# Tester_Schematic.net
KiCad netlist of a schematic drawn in EAGLE
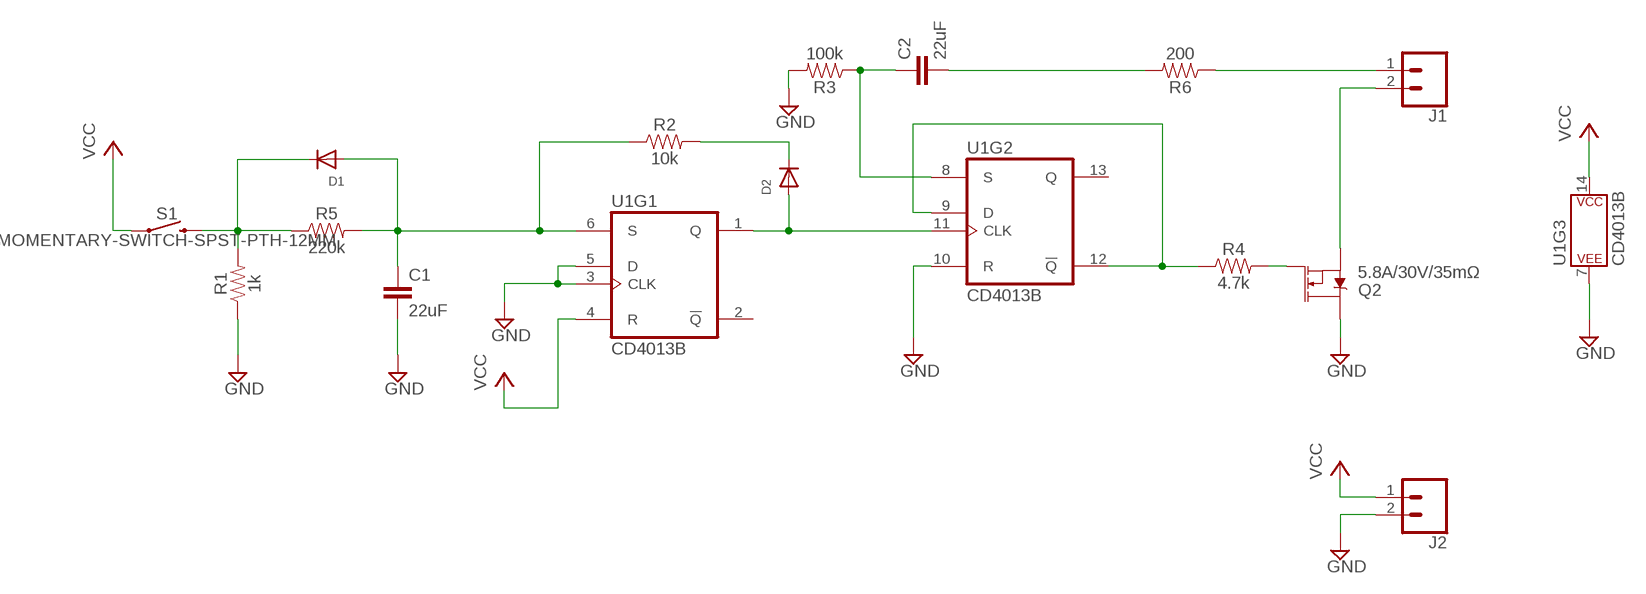
[diagram p0: schematic, sheet 1]

(export (version "E")
  (design (tool "Eeschema 10.0.6"))
  (components
    (comp (ref "C1")
      (value "22uF")
      (footprint "eagle-import:0805")
      (libsource (lib "eagle-import") (part "22UF-0805-6.3V-20%"))
    )
    (comp (ref "C2")
      (value "22uF")
      (footprint "eagle-import:0805")
      (libsource (lib "eagle-import") (part "22UF-0805-6.3V-20%"))
    )
    (comp (ref "D1")
      (value "DIODESOD-123")
      (footprint "eagle-import:SOD-123")
      (libsource (lib "eagle-import") (part "DIODESOD-123"))
    )
    (comp (ref "D2")
      (value "DIODESOD-123")
      (footprint "eagle-import:SOD-123")
      (libsource (lib "eagle-import") (part "DIODESOD-123"))
    )
    (comp (ref "J1")
      (value "CONN_02")
      (footprint "eagle-import:1X02")
      (libsource (lib "eagle-import") (part "CONN_02"))
    )
    (comp (ref "J2")
      (value "CONN_02")
      (footprint "eagle-import:1X02")
      (libsource (lib "eagle-import") (part "CONN_02"))
    )
    (comp (ref "Q2")
      (value "5.8A/30V/35mΩ")
      (footprint "eagle-import:SOT23-3")
      (libsource (lib "eagle-import") (part "MOSFET-NCH-AO3404A"))
    )
    (comp (ref "R1")
      (value "1k")
      (footprint "eagle-import:0603")
      (libsource (lib "eagle-import") (part "1KOHM-0603-1/10W-1%"))
    )
    (comp (ref "R2")
      (value "10k")
      (footprint "eagle-import:0603")
      (libsource (lib "eagle-import") (part "10KOHM-0603-1/10W-1%"))
    )
    (comp (ref "R3")
      (value "100k")
      (footprint "eagle-import:0603")
      (libsource (lib "eagle-import") (part "100KOHM-0603-1/10W-1%"))
    )
    (comp (ref "R4")
      (value "4.7k")
      (footprint "eagle-import:0603")
      (libsource (lib "eagle-import") (part "4.7KOHM-0603-1/10W-1%"))
    )
    (comp (ref "R5")
      (value "220k")
      (footprint "eagle-import:0603")
      (libsource (lib "eagle-import") (part "220KOHM-0603-1/10W-1%"))
    )
    (comp (ref "R6")
      (value "200")
      (footprint "eagle-import:0603")
      (libsource (lib "eagle-import") (part "200OHM-0603-1/10W-1%"))
    )
    (comp (ref "S1")
      (value "MOMENTARY-SWITCH-SPST-PTH-12MM")
      (footprint "eagle-import:TACTILE_SWITCH_PTH_12MM")
      (libsource (lib "eagle-import") (part "MOMENTARY-SWITCH-SPST-PTH-12MM"))
    )
    (comp (ref "U1")
      (value "CD4013B")
      (footprint "eagle-import:DIP14-KIT")
      (libsource (lib "eagle-import") (part "CD4013"))
    )
  )
  (nets
    (net (code "1") (name "GND") (class "Default")
      (node (ref "C1") (pin "2") (pinfunction "2_2") (pintype "passive"))
      (node (ref "J2") (pin "2") (pinfunction "2_2") (pintype "passive"))
      (node (ref "Q2") (pin "3") (pinfunction "D_3") (pintype "bidirectional"))
      (node (ref "R1") (pin "1") (pinfunction "1_1") (pintype "passive"))
      (node (ref "R3") (pin "2") (pinfunction "2_2") (pintype "passive"))
      (node (ref "U1") (pin "10") (pinfunction "R_10") (pintype "input"))
      (node (ref "U1") (pin "3") (pinfunction "CLK_3") (pintype "input"))
      (node (ref "U1") (pin "5") (pinfunction "D_5") (pintype "input"))
      (node (ref "U1") (pin "7") (pinfunction "P$V-_7") (pintype "bidirectional"))
    )
    (net (code "2") (name "Net-(C2-Pad2)") (class "Default")
      (node (ref "C2") (pin "2") (pinfunction "2_2") (pintype "passive"))
      (node (ref "R6") (pin "2") (pinfunction "2_2") (pintype "passive"))
    )
    (net (code "3") (name "Net-(D2-PadC)") (class "Default")
      (node (ref "D2") (pin "C") (pinfunction "C_C") (pintype "passive"))
      (node (ref "R2") (pin "2") (pinfunction "2_2") (pintype "passive"))
    )
    (net (code "4") (name "Net-(J1-Pad1)") (class "Default")
      (node (ref "J1") (pin "1") (pinfunction "1_1") (pintype "passive"))
      (node (ref "R6") (pin "1") (pinfunction "1_1") (pintype "passive"))
    )
    (net (code "5") (name "Net-(Q2-G)") (class "Default")
      (node (ref "Q2") (pin "1") (pinfunction "G_1") (pintype "bidirectional"))
      (node (ref "R4") (pin "2") (pinfunction "2_2") (pintype "passive"))
    )
    (net (code "6") (name "Net-(Q2-S)") (class "Default")
      (node (ref "J1") (pin "2") (pinfunction "2_2") (pintype "passive"))
      (node (ref "Q2") (pin "2") (pinfunction "S_2") (pintype "bidirectional"))
    )
    (net (code "7") (name "Net-(S1-2)") (class "Default")
      (node (ref "D1") (pin "C") (pinfunction "C_C") (pintype "passive"))
      (node (ref "R1") (pin "2") (pinfunction "2_2") (pintype "passive"))
      (node (ref "R5") (pin "1") (pinfunction "1_1") (pintype "passive"))
      (node (ref "S1") (pin "3") (pinfunction "2_3") (pintype "passive"))
    )
    (net (code "8") (name "Net-(U1A-Q)") (class "Default")
      (node (ref "D2") (pin "A") (pinfunction "A_A") (pintype "passive"))
      (node (ref "U1") (pin "1") (pinfunction "Q_1") (pintype "output"))
      (node (ref "U1") (pin "11") (pinfunction "CLK_11") (pintype "input"))
    )
    (net (code "9") (name "Net-(U1A-S)") (class "Default")
      (node (ref "C1") (pin "1") (pinfunction "1_1") (pintype "passive"))
      (node (ref "D1") (pin "A") (pinfunction "A_A") (pintype "passive"))
      (node (ref "R2") (pin "1") (pinfunction "1_1") (pintype "passive"))
      (node (ref "R5") (pin "2") (pinfunction "2_2") (pintype "passive"))
      (node (ref "U1") (pin "6") (pinfunction "S_6") (pintype "input"))
    )
    (net (code "10") (name "Net-(U1B-D)") (class "Default")
      (node (ref "R4") (pin "1") (pinfunction "1_1") (pintype "passive"))
      (node (ref "U1") (pin "12") (pinfunction "~{Q}_12") (pintype "output"))
      (node (ref "U1") (pin "9") (pinfunction "D_9") (pintype "input"))
    )
    (net (code "11") (name "Net-(U1B-S)") (class "Default")
      (node (ref "C2") (pin "1") (pinfunction "1_1") (pintype "passive"))
      (node (ref "R3") (pin "1") (pinfunction "1_1") (pintype "passive"))
      (node (ref "U1") (pin "8") (pinfunction "S_8") (pintype "input"))
    )
    (net (code "12") (name "VCC") (class "Default")
      (node (ref "J2") (pin "1") (pinfunction "1_1") (pintype "passive"))
      (node (ref "S1") (pin "1") (pinfunction "1_1") (pintype "passive"))
      (node (ref "U1") (pin "14") (pinfunction "P$V+_14") (pintype "bidirectional"))
      (node (ref "U1") (pin "4") (pinfunction "R_4") (pintype "input"))
    )
    (net (code "13") (name "unconnected-(U1A-~{Q}-Pad2)") (class "Default")
      (node (ref "U1") (pin "2") (pinfunction "~{Q}_2") (pintype "output"))
    )
    (net (code "14") (name "unconnected-(U1B-Q-Pad13)") (class "Default")
      (node (ref "U1") (pin "13") (pinfunction "Q_13") (pintype "output"))
    )
  )
)
